# RFstick.net
KiCad netlist of a schematic drawn in EAGLE
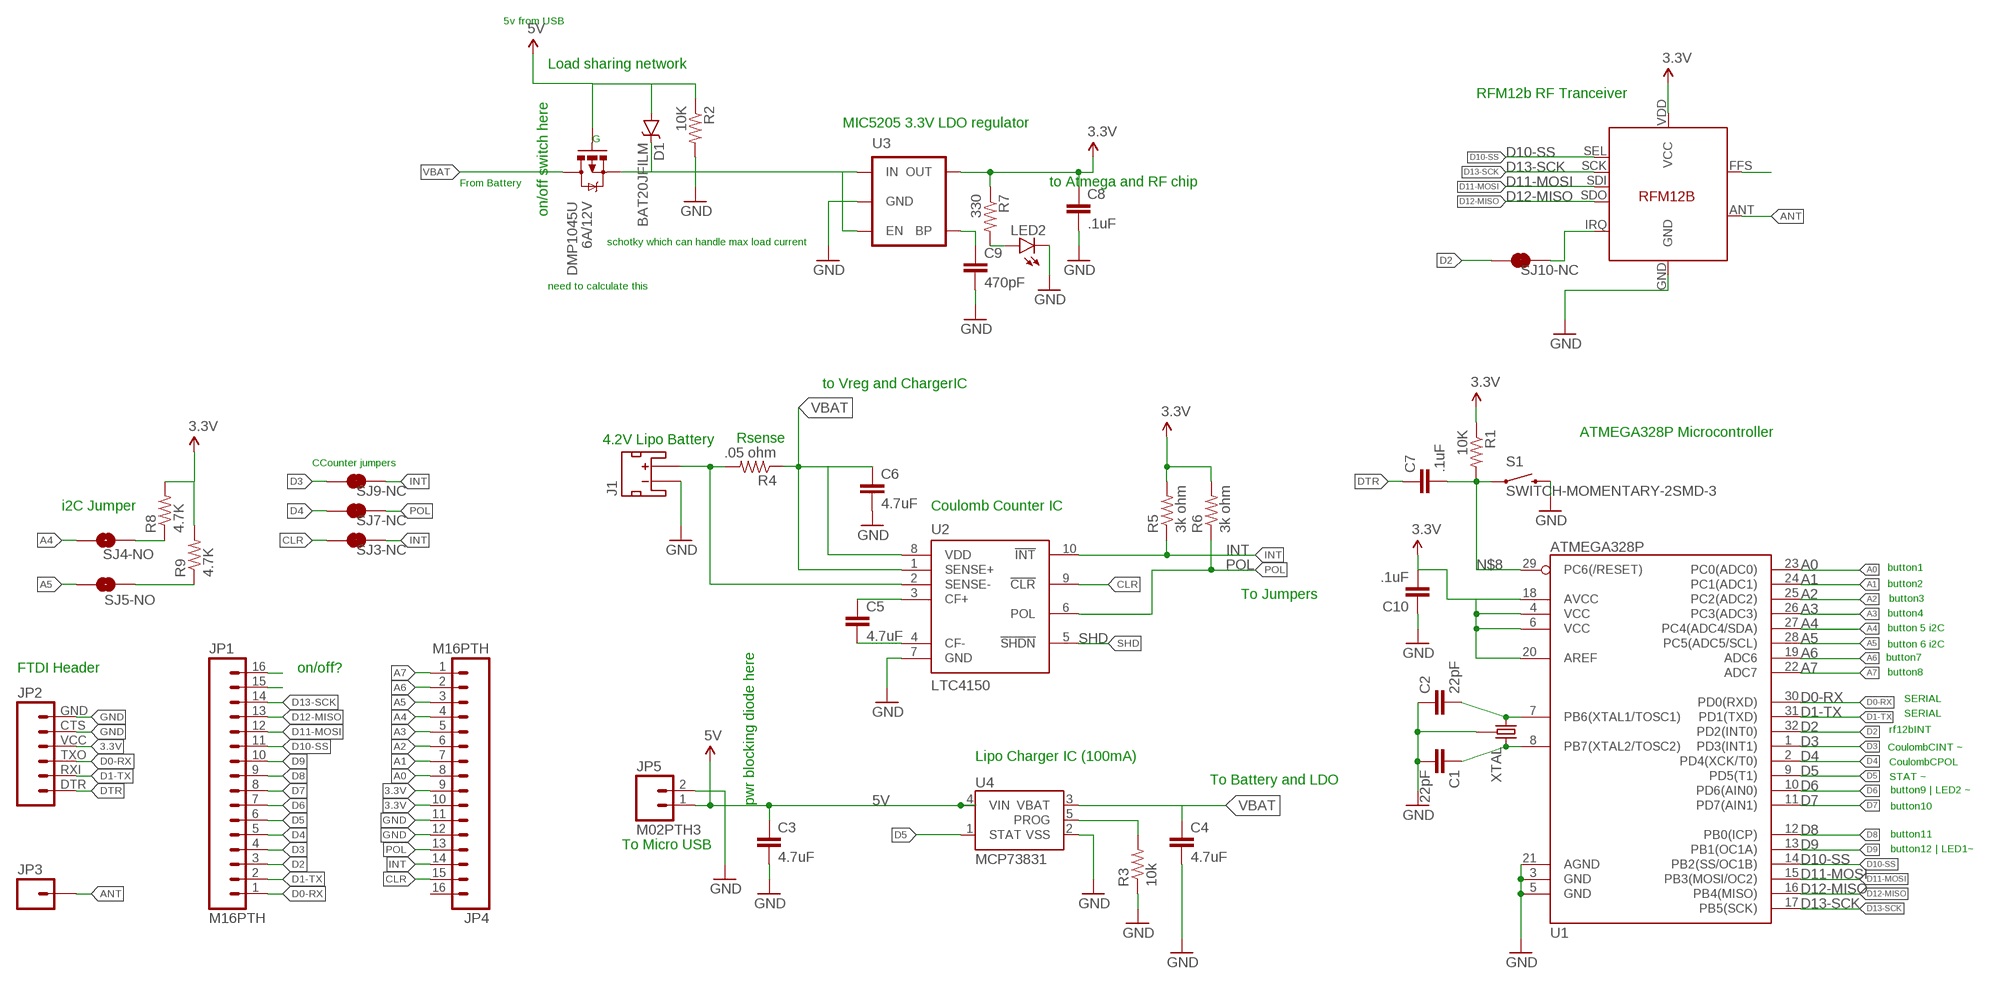
[diagram p0: schematic, sheet 1]

(export (version "E")
  (design (tool "Eeschema 10.0.6"))
  (components
    (comp (ref "C1")
      (value "22pF")
      (footprint "eagle-import:0603-CAP")
      (fields (field (name "MPN") "04025A220JAT2A"))
      (libsource (lib "eagle-import") (part "22PF-50V-5%(0603)"))
    )
    (comp (ref "C2")
      (value "22pF")
      (footprint "eagle-import:0603-CAP")
      (fields (field (name "MPN") "04025A220JAT2A"))
      (libsource (lib "eagle-import") (part "22PF-50V-5%(0603)"))
    )
    (comp (ref "C3")
      (value "4.7uF")
      (footprint "eagle-import:0603-CAP")
      (fields (field (name "MPN") "F981A475MMA"))
      (libsource (lib "eagle-import") (part "4.7UF-6.3V-10%(0603)0603"))
    )
    (comp (ref "C4")
      (value "4.7uF")
      (footprint "eagle-import:0603-CAP")
      (fields (field (name "MPN") "F981A475MMA"))
      (libsource (lib "eagle-import") (part "4.7UF-6.3V-10%(0603)0603"))
    )
    (comp (ref "C5")
      (value "4.7uF")
      (footprint "eagle-import:0603-CAP")
      (fields (field (name "MPN") "F981A475MMA"))
      (libsource (lib "eagle-import") (part "4.7UF-6.3V-10%(0603)0603"))
    )
    (comp (ref "C6")
      (value "4.7uF")
      (footprint "eagle-import:0603-CAP")
      (fields (field (name "MPN") "F981A475MMA"))
      (libsource (lib "eagle-import") (part "4.7UF-6.3V-10%(0603)0603"))
    )
    (comp (ref "C7")
      (value ".1uF")
      (footprint "eagle-import:0603-CAP")
      (fields (field (name "MPN") "MC0603B104M500CT"))
      (libsource (lib "eagle-import") (part "22PF-50V-5%(0603)"))
    )
    (comp (ref "C8")
      (value ".1uF")
      (footprint "eagle-import:0603-CAP")
      (fields (field (name "MPN") "MC0603B104M500CT"))
      (libsource (lib "eagle-import") (part "4.7UF-6.3V-10%(0603)0603"))
    )
    (comp (ref "C9")
      (value "470pF")
      (footprint "eagle-import:0603-CAP")
      (fields (field (name "MPN") "06031C471JAT2A"))
      (libsource (lib "eagle-import") (part "470PF-50V-5%(0603)SMD"))
    )
    (comp (ref "C10")
      (value ".1uF")
      (footprint "eagle-import:0603-CAP")
      (fields (field (name "MPN") "MC0603B104M500CT"))
      (libsource (lib "eagle-import") (part "22PF-50V-5%(0603)"))
    )
    (comp (ref "D1")
      (value "BAT20JFILM")
      (footprint "eagle-import:SOD-323")
      (libsource (lib "eagle-import") (part "BAT20JFILM"))
    )
    (comp (ref "DMP1045U")
      (value "6A/12V")
      (footprint "eagle-import:SOT23-3")
      (libsource (lib "eagle-import") (part "MOSFET-PCHANNELDMG2307L"))
    )
    (comp (ref "J1")
      (value "JST_2MM_MALE")
      (footprint "eagle-import:JST-2-SMD")
      (libsource (lib "eagle-import") (part "JST_2MM_MALE"))
    )
    (comp (ref "JP1")
      (value "M16PTH")
      (footprint "eagle-import:1X16")
      (libsource (lib "eagle-import") (part "M16PTH"))
    )
    (comp (ref "JP2")
      (value "M06SIP")
      (footprint "eagle-import:1X06")
      (libsource (lib "eagle-import") (part "M06SIP"))
    )
    (comp (ref "JP3")
      (value "M01PTH")
      (footprint "eagle-import:1X01")
      (libsource (lib "eagle-import") (part "M01PTH"))
    )
    (comp (ref "JP4")
      (value "M16PTH")
      (footprint "eagle-import:1X16")
      (libsource (lib "eagle-import") (part "M16PTH"))
    )
    (comp (ref "JP5")
      (value "M02PTH3")
      (footprint "eagle-import:1X02_LONGPADS")
      (libsource (lib "eagle-import") (part "M02PTH3"))
    )
    (comp (ref "LED2")
      (value "LED0603")
      (footprint "eagle-import:LED-0603")
      (fields (field (name "MPN") "150060RS75000"))
      (libsource (lib "eagle-import") (part "LED0603"))
    )
    (comp (ref "R1")
      (value "10K")
      (footprint "eagle-import:0603-RES")
      (fields (field (name "MPN") "CRCW060310K0FKEAHP"))
      (libsource (lib "eagle-import") (part "10KOHM1/10W1%(0603)0603"))
    )
    (comp (ref "R2")
      (value "10K")
      (footprint "eagle-import:0603-RES")
      (fields (field (name "MPN") "CRCW060310K0FKEAHP"))
      (libsource (lib "eagle-import") (part "10KOHM1/10W1%(0603)0603"))
    )
    (comp (ref "R3")
      (value "10k")
      (footprint "eagle-import:0603-RES")
      (fields (field (name "MF") "VISHAY/DALE") (field (name "MPN") "CRCW06032K00FKEA"))
      (libsource (lib "eagle-import") (part "2.0KOHM1/10W5%(0603)"))
    )
    (comp (ref "R4")
      (value ".05 ohm")
      (footprint "eagle-import:0603-RES")
      (fields (field (name "MPN") "MC0063W060311R0"))
      (libsource (lib "eagle-import") (part "330OHM1/10W1%(0603)"))
    )
    (comp (ref "R5")
      (value "3k ohm")
      (footprint "eagle-import:0603-RES")
      (fields (field (name "MPN") "SR1-0603-230"))
      (libsource (lib "eagle-import") (part "330OHM1/10W1%(0603)"))
    )
    (comp (ref "R6")
      (value "3k ohm")
      (footprint "eagle-import:0603-RES")
      (fields (field (name "MPN") "SR1-0603-230"))
      (libsource (lib "eagle-import") (part "330OHM1/10W1%(0603)"))
    )
    (comp (ref "R7")
      (value "330")
      (footprint "eagle-import:0603-RES")
      (libsource (lib "eagle-import") (part "330OHM1/10W1%(0603)"))
    )
    (comp (ref "R8")
      (value "4.7K")
      (footprint "eagle-import:0603-RES")
      (fields (field (name "MF") "VISHAY/DALE") (field (name "MPN") "CRCW06034K70FKEA"))
      (libsource (lib "eagle-import") (part "4.7KOHM-1/10W-1%(0603)"))
    )
    (comp (ref "R9")
      (value "4.7K")
      (footprint "eagle-import:0603-RES")
      (fields (field (name "MF") "VISHAY/DALE") (field (name "MPN") "CRCW06034K70FKEA"))
      (libsource (lib "eagle-import") (part "4.7KOHM-1/10W-1%(0603)"))
    )
    (comp (ref "S1")
      (value "SWITCH-MOMENTARY-2SMD-3")
      (footprint "eagle-import:TACTILE_SWITCH_SMD-3")
      (libsource (lib "eagle-import") (part "SWITCH-MOMENTARY-2SMD-3"))
    )
    (comp (ref "SJ3-NC")
      (value "JUMPER-PAD-2-NC_BY_TRACENO_SILK")
      (footprint "eagle-import:PAD-JUMPER-2-NC_BY_TRACE_NO_SILK")
      (libsource (lib "eagle-import") (part "JUMPER-PAD-2-NC_BY_TRACENO_SILK"))
    )
    (comp (ref "SJ4-NO")
      (value "JUMPER-PAD-2-NO")
      (footprint "eagle-import:PAD-JUMPER-2-NO_NO_SILK")
      (libsource (lib "eagle-import") (part "JUMPER-PAD-2-NO"))
    )
    (comp (ref "SJ5-NO")
      (value "JUMPER-PAD-2-NO")
      (footprint "eagle-import:PAD-JUMPER-2-NO_NO_SILK")
      (libsource (lib "eagle-import") (part "JUMPER-PAD-2-NO"))
    )
    (comp (ref "SJ7-NC")
      (value "JUMPER-PAD-2-NC_BY_TRACENO_SILK")
      (footprint "eagle-import:PAD-JUMPER-2-NC_BY_TRACE_NO_SILK")
      (libsource (lib "eagle-import") (part "JUMPER-PAD-2-NC_BY_TRACENO_SILK"))
    )
    (comp (ref "SJ9-NC")
      (value "JUMPER-PAD-2-NC_BY_TRACENO_SILK")
      (footprint "eagle-import:PAD-JUMPER-2-NC_BY_TRACE_NO_SILK")
      (libsource (lib "eagle-import") (part "JUMPER-PAD-2-NC_BY_TRACENO_SILK"))
    )
    (comp (ref "SJ10-NC")
      (value "JUMPER-PAD-2-NC_BY_TRACENO_SILK")
      (footprint "eagle-import:PAD-JUMPER-2-NC_BY_TRACE_NO_SILK")
      (libsource (lib "eagle-import") (part "JUMPER-PAD-2-NC_BY_TRACENO_SILK"))
    )
    (comp (ref "U$1")
      (value "XTAL")
      (footprint "eagle-import:CRYSTAL-SMD-5X3")
      (fields (field (name "MPN") "AA-16.000MALE-T"))
      (libsource (lib "eagle-import") (part "CRYSTAL-GROUNDED"))
    )
    (comp (ref "U$2")
      (value "RFM12B")
      (footprint "eagle-import:RFM12B")
      (libsource (lib "eagle-import") (part "RFM12B"))
    )
    (comp (ref "U1")
      (value "ATMEGA328P")
      (footprint "eagle-import:TQFP32-08")
      (libsource (lib "eagle-import") (part "ATMEGA328_SMT"))
    )
    (comp (ref "U2")
      (value "LTC4150")
      (footprint "eagle-import:MSOP10")
      (fields (field (name "MPN") "LTC4150CMS#PBF"))
      (libsource (lib "eagle-import") (part "LTC4150"))
    )
    (comp (ref "U3")
      (value "MIC52053.3V")
      (footprint "eagle-import:SOT23-5")
      (fields (field (name "MPN") "MIC5205-3.3YM5 TR"))
      (libsource (lib "eagle-import") (part "MIC52053.3V"))
    )
    (comp (ref "U4")
      (value "MCP73831")
      (footprint "eagle-import:SOT23-5")
      (fields (field (name "MPN") "MCP73831T-2ACI/OT"))
      (libsource (lib "eagle-import") (part "MCP73831"))
    )
  )
  (nets
    (net (code "1") (name "/N$8") (class "Default")
      (node (ref "C7") (pin "2") (pinfunction "2_2") (pintype "passive"))
      (node (ref "R1") (pin "2") (pinfunction "2_2") (pintype "passive"))
      (node (ref "S1") (pin "1") (pinfunction "1_1") (pintype "passive"))
      (node (ref "U1") (pin "29") (pinfunction "PC6(/RESET)_29") (pintype "bidirectional"))
    )
    (net (code "2") (name "3.3V") (class "Default")
      (node (ref "C10") (pin "2") (pinfunction "2_2") (pintype "passive"))
      (node (ref "C8") (pin "1") (pinfunction "1_1") (pintype "passive"))
      (node (ref "JP2") (pin "VCC") (pinfunction "4_VCC") (pintype "passive"))
      (node (ref "JP4") (pin "10") (pinfunction "10_10") (pintype "passive"))
      (node (ref "JP4") (pin "9") (pinfunction "9_9") (pintype "passive"))
      (node (ref "R1") (pin "1") (pinfunction "1_1") (pintype "passive"))
      (node (ref "R5") (pin "2") (pinfunction "2_2") (pintype "passive"))
      (node (ref "R6") (pin "2") (pinfunction "2_2") (pintype "passive"))
      (node (ref "R7") (pin "1") (pinfunction "1_1") (pintype "passive"))
      (node (ref "R8") (pin "2") (pinfunction "2_2") (pintype "passive"))
      (node (ref "R9") (pin "2") (pinfunction "2_2") (pintype "passive"))
      (node (ref "U$2") (pin "VDD") (pinfunction "VCC_VDD") (pintype "power_in"))
      (node (ref "U1") (pin "18") (pinfunction "AVCC_18") (pintype "bidirectional"))
      (node (ref "U1") (pin "20") (pinfunction "AREF_20") (pintype "bidirectional"))
      (node (ref "U1") (pin "4") (pinfunction "VCC_4") (pintype "bidirectional"))
      (node (ref "U1") (pin "6") (pinfunction "VCC_6") (pintype "bidirectional"))
      (node (ref "U3") (pin "5") (pinfunction "OUT_5") (pintype "passive"))
    )
    (net (code "3") (name "5V") (class "Default")
      (node (ref "C3") (pin "1") (pinfunction "1_1") (pintype "passive"))
      (node (ref "D1") (pin "A") (pinfunction "A_A") (pintype "passive"))
      (node (ref "DMP1045U") (pin "1") (pinfunction "G_1") (pintype "passive"))
      (node (ref "JP5") (pin "1") (pinfunction "1_1") (pintype "passive"))
      (node (ref "R2") (pin "1") (pinfunction "1_1") (pintype "passive"))
      (node (ref "U4") (pin "4") (pinfunction "VIN_4") (pintype "power_in"))
    )
    (net (code "4") (name "A0") (class "Default")
      (node (ref "JP4") (pin "8") (pinfunction "8_8") (pintype "passive"))
      (node (ref "U1") (pin "23") (pinfunction "PC0(ADC0)_23") (pintype "bidirectional"))
    )
    (net (code "5") (name "A1") (class "Default")
      (node (ref "JP4") (pin "7") (pinfunction "7_7") (pintype "passive"))
      (node (ref "U1") (pin "24") (pinfunction "PC1(ADC1)_24") (pintype "bidirectional"))
    )
    (net (code "6") (name "A2") (class "Default")
      (node (ref "JP4") (pin "6") (pinfunction "6_6") (pintype "passive"))
      (node (ref "U1") (pin "25") (pinfunction "PC2(ADC2)_25") (pintype "bidirectional"))
    )
    (net (code "7") (name "A3") (class "Default")
      (node (ref "JP4") (pin "5") (pinfunction "5_5") (pintype "passive"))
      (node (ref "U1") (pin "26") (pinfunction "PC3(ADC3)_26") (pintype "bidirectional"))
    )
    (net (code "8") (name "A4") (class "Default")
      (node (ref "JP4") (pin "4") (pinfunction "4_4") (pintype "passive"))
      (node (ref "SJ4-NO") (pin "1") (pinfunction "1_1") (pintype "passive"))
      (node (ref "U1") (pin "27") (pinfunction "PC4(ADC4/SDA)_27") (pintype "bidirectional"))
    )
    (net (code "9") (name "A5") (class "Default")
      (node (ref "JP4") (pin "3") (pinfunction "3_3") (pintype "passive"))
      (node (ref "SJ5-NO") (pin "1") (pinfunction "1_1") (pintype "passive"))
      (node (ref "U1") (pin "28") (pinfunction "PC5(ADC5/SCL)_28") (pintype "bidirectional"))
    )
    (net (code "10") (name "A6") (class "Default")
      (node (ref "JP4") (pin "2") (pinfunction "2_2") (pintype "passive"))
      (node (ref "U1") (pin "19") (pinfunction "ADC6_19") (pintype "bidirectional"))
    )
    (net (code "11") (name "A7") (class "Default")
      (node (ref "JP4") (pin "1") (pinfunction "1_1") (pintype "passive"))
      (node (ref "U1") (pin "22") (pinfunction "ADC7_22") (pintype "bidirectional"))
    )
    (net (code "12") (name "ANT") (class "Default")
      (node (ref "JP3") (pin "1") (pinfunction "1_1") (pintype "passive"))
      (node (ref "U$2") (pin "ANT") (pinfunction "ANT_ANT") (pintype "passive"))
    )
    (net (code "13") (name "CLR") (class "Default")
      (node (ref "JP4") (pin "15") (pinfunction "15_15") (pintype "passive"))
      (node (ref "SJ3-NC") (pin "1") (pinfunction "1_1") (pintype "passive"))
      (node (ref "U2") (pin "9") (pinfunction "~{CLR}_9") (pintype "bidirectional"))
    )
    (net (code "14") (name "D0-RX") (class "Default")
      (node (ref "JP1") (pin "1") (pinfunction "1_1") (pintype "passive"))
      (node (ref "JP2") (pin "TXO") (pinfunction "3_TXO") (pintype "passive"))
      (node (ref "U1") (pin "30") (pinfunction "PD0(RXD)_30") (pintype "bidirectional"))
    )
    (net (code "15") (name "D1-TX") (class "Default")
      (node (ref "JP1") (pin "2") (pinfunction "2_2") (pintype "passive"))
      (node (ref "JP2") (pin "RXI") (pinfunction "2_RXI") (pintype "passive"))
      (node (ref "U1") (pin "31") (pinfunction "PD1(TXD)_31") (pintype "bidirectional"))
    )
    (net (code "16") (name "D2") (class "Default")
      (node (ref "JP1") (pin "3") (pinfunction "3_3") (pintype "passive"))
      (node (ref "SJ10-NC") (pin "1") (pinfunction "1_1") (pintype "passive"))
      (node (ref "U1") (pin "32") (pinfunction "PD2(INT0)_32") (pintype "bidirectional"))
    )
    (net (code "17") (name "D3") (class "Default")
      (node (ref "JP1") (pin "4") (pinfunction "4_4") (pintype "passive"))
      (node (ref "SJ9-NC") (pin "1") (pinfunction "1_1") (pintype "passive"))
      (node (ref "U1") (pin "1") (pinfunction "PD3(INT1)_1") (pintype "bidirectional"))
    )
    (net (code "18") (name "D4") (class "Default")
      (node (ref "JP1") (pin "5") (pinfunction "5_5") (pintype "passive"))
      (node (ref "SJ7-NC") (pin "1") (pinfunction "1_1") (pintype "passive"))
      (node (ref "U1") (pin "2") (pinfunction "PD4(XCK/T0)_2") (pintype "bidirectional"))
    )
    (net (code "19") (name "D5") (class "Default")
      (node (ref "JP1") (pin "6") (pinfunction "6_6") (pintype "passive"))
      (node (ref "U1") (pin "9") (pinfunction "PD5(T1)_9") (pintype "bidirectional"))
      (node (ref "U4") (pin "1") (pinfunction "STAT_1") (pintype "output"))
    )
    (net (code "20") (name "D6") (class "Default")
      (node (ref "JP1") (pin "7") (pinfunction "7_7") (pintype "passive"))
      (node (ref "U1") (pin "10") (pinfunction "PD6(AIN0)_10") (pintype "bidirectional"))
    )
    (net (code "21") (name "D7") (class "Default")
      (node (ref "JP1") (pin "8") (pinfunction "8_8") (pintype "passive"))
      (node (ref "U1") (pin "11") (pinfunction "PD7(AIN1)_11") (pintype "bidirectional"))
    )
    (net (code "22") (name "D8") (class "Default")
      (node (ref "JP1") (pin "9") (pinfunction "9_9") (pintype "passive"))
      (node (ref "U1") (pin "12") (pinfunction "PB0(ICP)_12") (pintype "bidirectional"))
    )
    (net (code "23") (name "D9") (class "Default")
      (node (ref "JP1") (pin "10") (pinfunction "10_10") (pintype "passive"))
      (node (ref "U1") (pin "13") (pinfunction "PB1(OC1A)_13") (pintype "bidirectional"))
    )
    (net (code "24") (name "D10-SS") (class "Default")
      (node (ref "JP1") (pin "11") (pinfunction "11_11") (pintype "passive"))
      (node (ref "U$2") (pin "SEL") (pinfunction "SEL_SEL") (pintype "input"))
      (node (ref "U1") (pin "14") (pinfunction "PB2(SS/OC1B)_14") (pintype "bidirectional"))
    )
    (net (code "25") (name "D11-MOSI") (class "Default")
      (node (ref "JP1") (pin "12") (pinfunction "12_12") (pintype "passive"))
      (node (ref "U$2") (pin "SDI") (pinfunction "SDI_SDI") (pintype "input"))
      (node (ref "U1") (pin "15") (pinfunction "PB3(MOSI/OC2)_15") (pintype "bidirectional"))
    )
    (net (code "26") (name "D12-MISO") (class "Default")
      (node (ref "JP1") (pin "13") (pinfunction "13_13") (pintype "passive"))
      (node (ref "U$2") (pin "SDO") (pinfunction "SDO_SDO") (pintype "output"))
      (node (ref "U1") (pin "16") (pinfunction "PB4(MISO)_16") (pintype "bidirectional"))
    )
    (net (code "27") (name "D13-SCK") (class "Default")
      (node (ref "JP1") (pin "14") (pinfunction "14_14") (pintype "passive"))
      (node (ref "U$2") (pin "SCK") (pinfunction "SCK_SCK") (pintype "input"))
      (node (ref "U1") (pin "17") (pinfunction "PB5(SCK)_17") (pintype "bidirectional"))
    )
    (net (code "28") (name "DTR") (class "Default")
      (node (ref "C7") (pin "1") (pinfunction "1_1") (pintype "passive"))
      (node (ref "JP2") (pin "DTR") (pinfunction "1_DTR") (pintype "passive"))
    )
    (net (code "29") (name "GND") (class "Default")
      (node (ref "C1") (pin "2") (pinfunction "2_2") (pintype "passive"))
      (node (ref "C10") (pin "1") (pinfunction "1_1") (pintype "passive"))
      (node (ref "C2") (pin "1") (pinfunction "1_1") (pintype "passive"))
      (node (ref "C3") (pin "2") (pinfunction "2_2") (pintype "passive"))
      (node (ref "C4") (pin "2") (pinfunction "2_2") (pintype "passive"))
      (node (ref "C6") (pin "2") (pinfunction "2_2") (pintype "passive"))
      (node (ref "C8") (pin "2") (pinfunction "2_2") (pintype "passive"))
      (node (ref "C9") (pin "2") (pinfunction "2_2") (pintype "passive"))
      (node (ref "J1") (pin "1") (pinfunction "-_1") (pintype "bidirectional"))
      (node (ref "JP2") (pin "CTS") (pinfunction "5_CTS") (pintype "passive"))
      (node (ref "JP2") (pin "GND") (pinfunction "6_GND") (pintype "passive"))
      (node (ref "JP4") (pin "11") (pinfunction "11_11") (pintype "passive"))
      (node (ref "JP4") (pin "12") (pinfunction "12_12") (pintype "passive"))
      (node (ref "JP5") (pin "2") (pinfunction "2_2") (pintype "passive"))
      (node (ref "LED2") (pin "C") (pinfunction "C_C") (pintype "passive"))
      (node (ref "R2") (pin "2") (pinfunction "2_2") (pintype "passive"))
      (node (ref "R3") (pin "1") (pinfunction "1_1") (pintype "passive"))
      (node (ref "S1") (pin "4") (pinfunction "2_4") (pintype "passive"))
      (node (ref "U$1") (pin "2") (pinfunction "3_2") (pintype "passive"))
      (node (ref "U$1") (pin "4") (pinfunction "3_4") (pintype "passive"))
      (node (ref "U$2") (pin "GND") (pinfunction "GND_GND") (pintype "power_in"))
      (node (ref "U1") (pin "21") (pinfunction "AGND_21") (pintype "bidirectional"))
      (node (ref "U1") (pin "3") (pinfunction "GND_3") (pintype "bidirectional"))
      (node (ref "U1") (pin "5") (pinfunction "GND_5") (pintype "bidirectional"))
      (node (ref "U2") (pin "7") (pinfunction "GND_7") (pintype "power_in"))
      (node (ref "U3") (pin "2") (pinfunction "GND_2") (pintype "input"))
      (node (ref "U4") (pin "2") (pinfunction "VSS_2") (pintype "power_in"))
    )
    (net (code "30") (name "INT") (class "Default")
      (node (ref "JP4") (pin "14") (pinfunction "14_14") (pintype "passive"))
      (node (ref "R5") (pin "1") (pinfunction "1_1") (pintype "passive"))
      (node (ref "SJ3-NC") (pin "2") (pinfunction "2_2") (pintype "passive"))
      (node (ref "SJ9-NC") (pin "2") (pinfunction "2_2") (pintype "passive"))
      (node (ref "U2") (pin "10") (pinfunction "~{INT}_10") (pintype "bidirectional"))
    )
    (net (code "31") (name "Net-(DMP1045U-S)") (class "Default")
      (node (ref "D1") (pin "C") (pinfunction "C_C") (pintype "passive"))
      (node (ref "DMP1045U") (pin "2") (pinfunction "S_2") (pintype "passive"))
      (node (ref "U3") (pin "1") (pinfunction "IN_1") (pintype "input"))
      (node (ref "U3") (pin "3") (pinfunction "EN_3") (pintype "input"))
    )
    (net (code "32") (name "Net-(J1-+)") (class "Default")
      (node (ref "J1") (pin "2") (pinfunction "+_2") (pintype "bidirectional"))
      (node (ref "R4") (pin "2") (pinfunction "2_2") (pintype "passive"))
      (node (ref "U2") (pin "2") (pinfunction "SENSE-_2") (pintype "bidirectional"))
    )
    (net (code "33") (name "Net-(LED2-PadA)") (class "Default")
      (node (ref "LED2") (pin "A") (pinfunction "A_A") (pintype "passive"))
      (node (ref "R7") (pin "2") (pinfunction "2_2") (pintype "passive"))
    )
    (net (code "34") (name "Net-(R8-Pad1)") (class "Default")
      (node (ref "R8") (pin "1") (pinfunction "1_1") (pintype "passive"))
      (node (ref "SJ4-NO") (pin "2") (pinfunction "2_2") (pintype "passive"))
    )
    (net (code "35") (name "Net-(R9-Pad1)") (class "Default")
      (node (ref "R9") (pin "1") (pinfunction "1_1") (pintype "passive"))
      (node (ref "SJ5-NO") (pin "2") (pinfunction "2_2") (pintype "passive"))
    )
    (net (code "36") (name "Net-(SJ10-NC-Pad2)") (class "Default")
      (node (ref "SJ10-NC") (pin "2") (pinfunction "2_2") (pintype "passive"))
      (node (ref "U$2") (pin "IRQ") (pinfunction "IRQ_IRQ") (pintype "open_collector"))
    )
    (net (code "37") (name "Net-(U$1-1)") (class "Default")
      (node (ref "C2") (pin "2") (pinfunction "2_2") (pintype "passive"))
      (node (ref "U$1") (pin "3") (pinfunction "1_3") (pintype "passive"))
      (node (ref "U1") (pin "7") (pinfunction "PB6(XTAL1/TOSC1)_7") (pintype "bidirectional"))
    )
    (net (code "38") (name "Net-(U$1-2)") (class "Default")
      (node (ref "C1") (pin "1") (pinfunction "1_1") (pintype "passive"))
      (node (ref "U$1") (pin "1") (pinfunction "2_1") (pintype "passive"))
      (node (ref "U1") (pin "8") (pinfunction "PB7(XTAL2/TOSC2)_8") (pintype "bidirectional"))
    )
    (net (code "39") (name "Net-(U2-CF+)") (class "Default")
      (node (ref "C5") (pin "1") (pinfunction "1_1") (pintype "passive"))
      (node (ref "U2") (pin "3") (pinfunction "CF+_3") (pintype "bidirectional"))
    )
    (net (code "40") (name "Net-(U2-CF-)") (class "Default")
      (node (ref "C5") (pin "2") (pinfunction "2_2") (pintype "passive"))
      (node (ref "U2") (pin "4") (pinfunction "CF-_4") (pintype "bidirectional"))
    )
    (net (code "41") (name "Net-(U3-BP)") (class "Default")
      (node (ref "C9") (pin "1") (pinfunction "1_1") (pintype "passive"))
      (node (ref "U3") (pin "4") (pinfunction "BP_4") (pintype "input"))
    )
    (net (code "42") (name "Net-(U4-PROG)") (class "Default")
      (node (ref "R3") (pin "2") (pinfunction "2_2") (pintype "passive"))
      (node (ref "U4") (pin "5") (pinfunction "PROG_5") (pintype "input"))
    )
    (net (code "43") (name "POL") (class "Default")
      (node (ref "JP4") (pin "13") (pinfunction "13_13") (pintype "passive"))
      (node (ref "R6") (pin "1") (pinfunction "1_1") (pintype "passive"))
      (node (ref "SJ7-NC") (pin "2") (pinfunction "2_2") (pintype "passive"))
      (node (ref "U2") (pin "6") (pinfunction "POL_6") (pintype "bidirectional"))
    )
    (net (code "44") (name "SHD") (class "Default")
      (node (ref "U2") (pin "5") (pinfunction "~{SHDN}_5") (pintype "input"))
    )
    (net (code "45") (name "VBAT") (class "Default")
      (node (ref "C4") (pin "1") (pinfunction "1_1") (pintype "passive"))
      (node (ref "C6") (pin "1") (pinfunction "1_1") (pintype "passive"))
      (node (ref "DMP1045U") (pin "3") (pinfunction "D_3") (pintype "passive"))
      (node (ref "R4") (pin "1") (pinfunction "1_1") (pintype "passive"))
      (node (ref "U2") (pin "1") (pinfunction "SENSE+_1") (pintype "bidirectional"))
      (node (ref "U2") (pin "8") (pinfunction "VDD_8") (pintype "power_in"))
      (node (ref "U4") (pin "3") (pinfunction "VBAT_3") (pintype "power_in"))
    )
    (net (code "46") (name "unconnected-(J1-PAD1-PadNC1)") (class "Default")
      (node (ref "J1") (pin "NC1") (pinfunction "PAD1_NC1") (pintype "bidirectional"))
    )
    (net (code "47") (name "unconnected-(J1-PAD2-PadNC2)") (class "Default")
      (node (ref "J1") (pin "NC2") (pinfunction "PAD2_NC2") (pintype "bidirectional"))
    )
    (net (code "48") (name "unconnected-(JP1-Pad15)") (class "Default")
      (node (ref "JP1") (pin "15") (pinfunction "15_15") (pintype "passive"))
    )
    (net (code "49") (name "unconnected-(JP1-Pad16)") (class "Default")
      (node (ref "JP1") (pin "16") (pinfunction "16_16") (pintype "passive"))
    )
    (net (code "50") (name "unconnected-(JP4-Pad16)") (class "Default")
      (node (ref "JP4") (pin "16") (pinfunction "16_16") (pintype "passive"))
    )
    (net (code "51") (name "unconnected-(U$2-PadFFS)") (class "Default")
      (node (ref "U$2") (pin "FFS") (pinfunction "FFS_FFS") (pintype "bidirectional"))
    )
  )
)
